# main_Rev1.net
KiCad netlist of a schematic drawn in Altium Designer
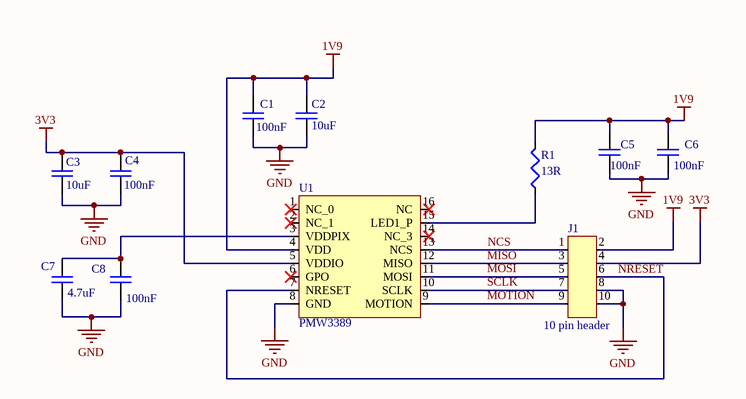
[diagram p0: main_Rev1.SchDoc]

(export (version "E")
  (design (tool "Eeschema 10.0.6"))
  (components
    (comp (ref "C1")
      (value "100nF")
      (footprint "C0603")
      (description "C0603")
      (fields (field (name "Comment") "02016D104KAT2A"))
      (libsource (lib "PMW3389_SCHlib") (part "02016D104KAT2A"))
    )
    (comp (ref "C2")
      (value "10uF")
      (footprint "C0805")
      (description "C0805")
      (fields (field (name "Comment") "08053C105KAT2A"))
      (libsource (lib "Passive components") (part "08053C105KAT2A"))
    )
    (comp (ref "C3")
      (value "10uF")
      (footprint "C0805")
      (description "C0805")
      (fields (field (name "Comment") "08053C105KAT2A"))
      (libsource (lib "Passive components") (part "08053C105KAT2A"))
    )
    (comp (ref "C4")
      (value "100nF")
      (footprint "C0603")
      (description "C0603")
      (fields (field (name "Comment") "02016D104KAT2A"))
      (libsource (lib "PMW3389_SCHlib") (part "02016D104KAT2A"))
    )
    (comp (ref "C5")
      (value "100nF")
      (footprint "C0603")
      (description "Decoupling LED_P.")
      (fields (field (name "Comment") "02016D104KAT2A"))
      (libsource (lib "PMW3389_SCHlib") (part "02016D104KAT2A"))
    )
    (comp (ref "C6")
      (value "100nF")
      (footprint "C0603")
      (description "Decoupling LED_P.")
      (fields (field (name "Comment") "02016D104KAT2A"))
      (libsource (lib "PMW3389_SCHlib") (part "02016D104KAT2A"))
    )
    (comp (ref "C7")
      (value "4.7uF")
      (footprint "C0805")
      (description "C0805")
      (fields (field (name "Comment") "08053C105KAT2A"))
      (libsource (lib "Passive components") (part "08053C105KAT2A"))
    )
    (comp (ref "C8")
      (value "100nF")
      (footprint "C0603")
      (description "C0603")
      (fields (field (name "Comment") "02016D104KAT2A"))
      (libsource (lib "PMW3389_SCHlib") (part "02016D104KAT2A"))
    )
    (comp (ref "J1")
      (value "10 pin header")
      (footprint "10 pin header")
      (libsource (lib "PMW3389_SCHlib") (part "10 pin header"))
    )
    (comp (ref "R1")
      (value "13R")
      (footprint "R0603")
      (description "Current limiter LED_P")
      (fields (field (name "Comment") "CPF-A-0603B100KE1"))
      (libsource (lib "PMW3389_SCHlib") (part "CPF-A-0603B100KE1"))
    )
    (comp (ref "U1")
      (value "PMW3389")
      (footprint "PMW3389")
      (libsource (lib "PMW3389_SCHlib") (part "PMW3389"))
    )
  )
  (nets
    (net (code "1") (name "/MISO") (class "Default")
      (node (ref "J1") (pin "3") (pintype "passive"))
      (node (ref "U1") (pin "12") (pinfunction "MISO_12") (pintype "passive"))
    )
    (net (code "4") (name "/NCS") (class "Default")
      (node (ref "J1") (pin "1") (pintype "passive"))
      (node (ref "U1") (pin "13") (pinfunction "NCS_13") (pintype "passive"))
    )
    (net (code "5") (name "/NRESET") (class "Default")
      (node (ref "J1") (pin "6") (pintype "passive"))
      (node (ref "U1") (pin "7") (pinfunction "NRESET_7") (pintype "passive"))
    )
    (net (code "7") (name "1V9") (class "Default")
      (node (ref "C1") (pin "2") (pinfunction "2_2") (pintype "passive"))
      (node (ref "C2") (pin "2") (pinfunction "2_2") (pintype "passive"))
      (node (ref "C5") (pin "2") (pinfunction "2_2") (pintype "passive"))
      (node (ref "C6") (pin "2") (pinfunction "2_2") (pintype "passive"))
      (node (ref "J1") (pin "2") (pintype "passive"))
      (node (ref "R1") (pin "2") (pinfunction "2_2") (pintype "passive"))
      (node (ref "U1") (pin "4") (pinfunction "VDD_4") (pintype "passive"))
    )
    (net (code "8") (name "3V3") (class "Default")
      (node (ref "C3") (pin "2") (pinfunction "2_2") (pintype "passive"))
      (node (ref "C4") (pin "2") (pinfunction "2_2") (pintype "passive"))
      (node (ref "J1") (pin "4") (pintype "passive"))
      (node (ref "U1") (pin "5") (pinfunction "VDDIO_5") (pintype "passive"))
    )
    (net (code "9") (name "GND") (class "Default")
      (node (ref "C1") (pin "1") (pinfunction "1_1") (pintype "passive"))
      (node (ref "C2") (pin "1") (pinfunction "1_1") (pintype "passive"))
      (node (ref "C3") (pin "1") (pinfunction "1_1") (pintype "passive"))
      (node (ref "C4") (pin "1") (pinfunction "1_1") (pintype "passive"))
      (node (ref "C5") (pin "1") (pinfunction "1_1") (pintype "passive"))
      (node (ref "C6") (pin "1") (pinfunction "1_1") (pintype "passive"))
      (node (ref "C7") (pin "1") (pinfunction "1_1") (pintype "passive"))
      (node (ref "C8") (pin "1") (pinfunction "1_1") (pintype "passive"))
      (node (ref "J1") (pin "10") (pintype "passive"))
      (node (ref "J1") (pin "8") (pintype "passive"))
      (node (ref "U1") (pin "8") (pinfunction "GND_8") (pintype "passive"))
    )
    (net (code "10") (name "Net-(U1-LED1_P)") (class "Default")
      (node (ref "R1") (pin "1") (pinfunction "1_1") (pintype "passive"))
      (node (ref "U1") (pin "15") (pinfunction "LED1_P_15") (pintype "passive"))
    )
    (net (code "11") (name "Net-(U1-MOSI)") (class "Default")
      (node (ref "J1") (pin "5") (pintype "passive"))
      (node (ref "U1") (pin "11") (pinfunction "MOSI_11") (pintype "passive"))
    )
    (net (code "12") (name "Net-(U1-MOTION)") (class "Default")
      (node (ref "J1") (pin "9") (pintype "passive"))
      (node (ref "U1") (pin "9") (pinfunction "MOTION_9") (pintype "passive"))
    )
    (net (code "13") (name "Net-(U1-SCLK)") (class "Default")
      (node (ref "J1") (pin "7") (pintype "passive"))
      (node (ref "U1") (pin "10") (pinfunction "SCLK_10") (pintype "passive"))
    )
    (net (code "14") (name "Net-(U1-VDDPIX)") (class "Default")
      (node (ref "C7") (pin "2") (pinfunction "2_2") (pintype "passive"))
      (node (ref "C8") (pin "2") (pinfunction "2_2") (pintype "passive"))
      (node (ref "U1") (pin "3") (pinfunction "VDDPIX_3") (pintype "passive"))
    )
    (net (code "15") (name "unconnected-(U1-GPO-Pad6)") (class "Default")
      (node (ref "U1") (pin "6") (pinfunction "GPO_6") (pintype "passive+no_connect"))
    )
    (net (code "16") (name "unconnected-(U1-NC-Pad16)") (class "Default")
      (node (ref "U1") (pin "16") (pinfunction "NC_16") (pintype "passive+no_connect"))
    )
    (net (code "17") (name "unconnected-(U1-NC_0-Pad1)") (class "Default")
      (node (ref "U1") (pin "1") (pinfunction "NC_0_1") (pintype "passive+no_connect"))
    )
    (net (code "18") (name "unconnected-(U1-NC_1-Pad2)") (class "Default")
      (node (ref "U1") (pin "2") (pinfunction "NC_1_2") (pintype "passive+no_connect"))
    )
    (net (code "19") (name "unconnected-(U1-NC_3-Pad14)") (class "Default")
      (node (ref "U1") (pin "14") (pinfunction "NC_3_14") (pintype "passive+no_connect"))
    )
  )
)
